# ZHSD-BOOT-STORAGE.net
KiCad netlist of a schematic drawn in Altium Designer
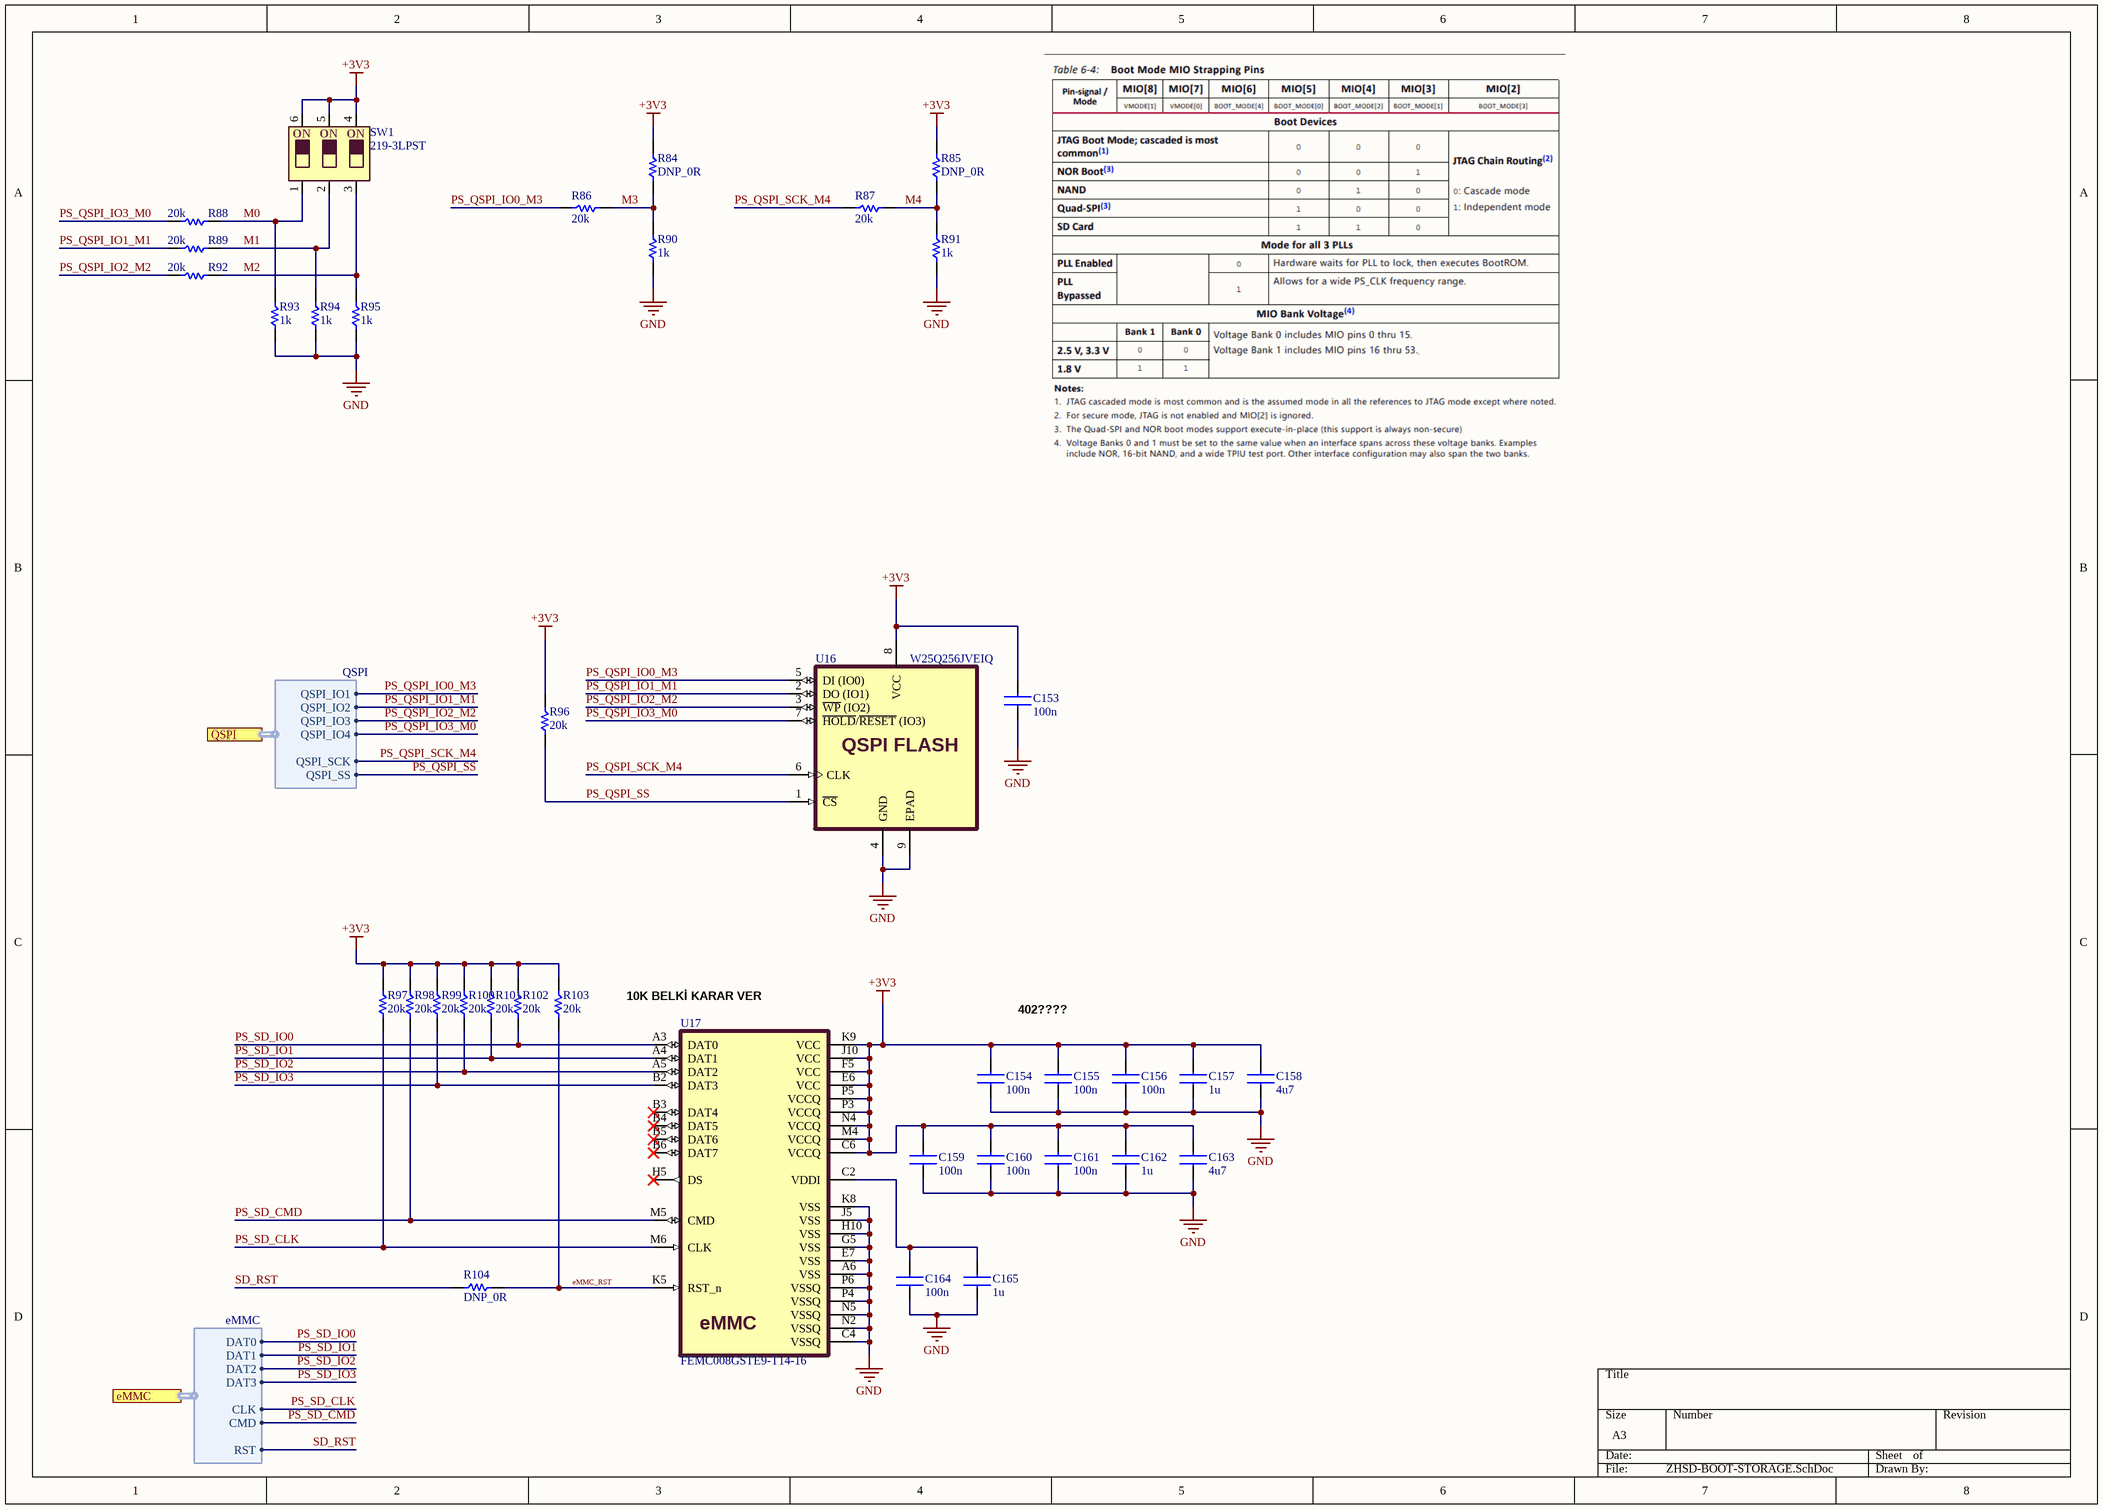
[diagram p0: ZHSD-BOOT-STORAGE.SchDoc]

(export (version "E")
  (design (tool "Eeschema 10.0.6"))
  (components
    (comp (ref "C153")
      (value "100n")
      (footprint "0603CAPC1608X09N")
      (description "CAP CER 0.1UF 16V X7R 0402 (1005) ±10%")
      (fields (field (name "MANUFACTURER") "Murata Electronics") (field (name "MPN") "GRM155R71C104KA88J"))
      (libsource (lib "UK_Library") (part "GRM155R71C104KA88J"))
    )
    (comp (ref "C154")
      (value "100n")
      (footprint "0603CAPC1608X09N")
      (description "CAP CER 0.1UF 16V X7R 0402 (1005) ±10%")
      (fields (field (name "MANUFACTURER") "Murata Electronics") (field (name "MPN") "GRM155R71C104KA88J"))
      (libsource (lib "UK_Library") (part "GRM155R71C104KA88J"))
    )
    (comp (ref "C155")
      (value "100n")
      (footprint "0603CAPC1608X09N")
      (description "CAP CER 0.1UF 16V X7R 0402 (1005) ±10%")
      (fields (field (name "MANUFACTURER") "Murata Electronics") (field (name "MPN") "GRM155R71C104KA88J"))
      (libsource (lib "UK_Library") (part "GRM155R71C104KA88J"))
    )
    (comp (ref "C156")
      (value "100n")
      (footprint "0603CAPC1608X09N")
      (description "CAP CER 0.1UF 16V X7R 0402 (1005) ±10%")
      (fields (field (name "MANUFACTURER") "Murata Electronics") (field (name "MPN") "GRM155R71C104KA88J"))
      (libsource (lib "UK_Library") (part "GRM155R71C104KA88J"))
    )
    (comp (ref "C157")
      (value "1u")
      (footprint "0603CAPC1608X09N")
      (description "CAP CER 1UF 25V X5R 0603 (1608) ±10%")
      (fields
        (field (name "MANUFACTURER") "Murata Power Solutions Inc.")
        (field (name "MPN") "GRM188R61E105KA12D")
      )
      (libsource (lib "UK_Library") (part "GRM188R61E105KA12D"))
    )
    (comp (ref "C158")
      (value "4u7")
      (footprint "0603CAPC1608X09N")
      (description "CAP CER 4.7UF 10V X5R 0603 (1608) ±10%")
      (fields
        (field (name "MANUFACTURER") "Samsung Electro-Mechanics")
        (field (name "MPN") "CL10A475KP8NNNC")
      )
      (libsource (lib "UK_Library") (part "CL10A475KP8NNNC"))
    )
    (comp (ref "C159")
      (value "100n")
      (footprint "0603CAPC1608X09N")
      (description "CAP CER 0.1UF 16V X7R 0402 (1005) ±10%")
      (fields (field (name "MANUFACTURER") "Murata Electronics") (field (name "MPN") "GRM155R71C104KA88J"))
      (libsource (lib "UK_Library") (part "GRM155R71C104KA88J"))
    )
    (comp (ref "C160")
      (value "100n")
      (footprint "0603CAPC1608X09N")
      (description "CAP CER 0.1UF 16V X7R 0402 (1005) ±10%")
      (fields (field (name "MANUFACTURER") "Murata Electronics") (field (name "MPN") "GRM155R71C104KA88J"))
      (libsource (lib "UK_Library") (part "GRM155R71C104KA88J"))
    )
    (comp (ref "C161")
      (value "100n")
      (footprint "0603CAPC1608X09N")
      (description "CAP CER 0.1UF 16V X7R 0402 (1005) ±10%")
      (fields (field (name "MANUFACTURER") "Murata Electronics") (field (name "MPN") "GRM155R71C104KA88J"))
      (libsource (lib "UK_Library") (part "GRM155R71C104KA88J"))
    )
    (comp (ref "C162")
      (value "1u")
      (footprint "0603CAPC1608X09N")
      (description "CAP CER 1UF 25V X5R 0603 (1608) ±10%")
      (fields
        (field (name "MANUFACTURER") "Murata Power Solutions Inc.")
        (field (name "MPN") "GRM188R61E105KA12D")
      )
      (libsource (lib "UK_Library") (part "GRM188R61E105KA12D"))
    )
    (comp (ref "C163")
      (value "4u7")
      (footprint "0603CAPC1608X09N")
      (description "CAP CER 4.7UF 10V X5R 0603 (1608) ±10%")
      (fields
        (field (name "MANUFACTURER") "Samsung Electro-Mechanics")
        (field (name "MPN") "CL10A475KP8NNNC")
      )
      (libsource (lib "UK_Library") (part "CL10A475KP8NNNC"))
    )
    (comp (ref "C164")
      (value "100n")
      (footprint "0603CAPC1608X09N")
      (description "CAP CER 0.1UF 16V X7R 0402 (1005) ±10%")
      (fields (field (name "MANUFACTURER") "Murata Electronics") (field (name "MPN") "GRM155R71C104KA88J"))
      (libsource (lib "UK_Library") (part "GRM155R71C104KA88J"))
    )
    (comp (ref "C165")
      (value "1u")
      (footprint "0603CAPC1608X09N")
      (description "CAP CER 1UF 25V X5R 0603 (1608) ±10%")
      (fields
        (field (name "MANUFACTURER") "Murata Power Solutions Inc.")
        (field (name "MPN") "GRM188R61E105KA12D")
      )
      (libsource (lib "UK_Library") (part "GRM188R61E105KA12D"))
    )
    (comp (ref "R84")
      (value "DNP_0R")
      (footprint "0402RESC1005X04N")
      (description "DO NOT POPULATE RESISTOR")
      (fields (field (name "MANUFACTURER") "***"))
      (libsource (lib "UK_Library") (part "DNP_RES"))
    )
    (comp (ref "R85")
      (value "DNP_0R")
      (footprint "0402RESC1005X04N")
      (description "DO NOT POPULATE RESISTOR")
      (fields (field (name "MANUFACTURER") "***"))
      (libsource (lib "UK_Library") (part "DNP_RES"))
    )
    (comp (ref "R86")
      (value "20k")
      (footprint "0402RESC1005X04N")
      (description "RES 20K OHM 1% 1/16W 0402 (1005)")
      (fields (field (name "MANUFACTURER") "YAGEO") (field (name "MPN") "RC0402FR-0720KL"))
      (libsource (lib "UK_Library") (part "RC0402FR-0720KL"))
    )
    (comp (ref "R87")
      (value "20k")
      (footprint "0402RESC1005X04N")
      (description "RES 20K OHM 1% 1/16W 0402 (1005)")
      (fields (field (name "MANUFACTURER") "YAGEO") (field (name "MPN") "RC0402FR-0720KL"))
      (libsource (lib "UK_Library") (part "RC0402FR-0720KL"))
    )
    (comp (ref "R88")
      (value "20k")
      (footprint "0402RESC1005X04N")
      (description "RES 20K OHM 1% 1/16W 0402 (1005)")
      (fields (field (name "MANUFACTURER") "YAGEO") (field (name "MPN") "RC0402FR-0720KL"))
      (libsource (lib "UK_Library") (part "RC0402FR-0720KL"))
    )
    (comp (ref "R89")
      (value "20k")
      (footprint "0402RESC1005X04N")
      (description "RES 20K OHM 1% 1/16W 0402 (1005)")
      (fields (field (name "MANUFACTURER") "YAGEO") (field (name "MPN") "RC0402FR-0720KL"))
      (libsource (lib "UK_Library") (part "RC0402FR-0720KL"))
    )
    (comp (ref "R90")
      (value "1k")
      (footprint "0402RESC1005X04N")
      (description "RES 1K OHM 5% 1/16W 0402 (1005)")
      (fields (field (name "MANUFACTURER") "YAGEO") (field (name "MPN") "RC0402JR-071KL"))
      (libsource (lib "UK_Library") (part "RC0402JR-071KL"))
    )
    (comp (ref "R91")
      (value "1k")
      (footprint "0402RESC1005X04N")
      (description "RES 1K OHM 5% 1/16W 0402 (1005)")
      (fields (field (name "MANUFACTURER") "YAGEO") (field (name "MPN") "RC0402JR-071KL"))
      (libsource (lib "UK_Library") (part "RC0402JR-071KL"))
    )
    (comp (ref "R92")
      (value "20k")
      (footprint "0402RESC1005X04N")
      (description "RES 20K OHM 1% 1/16W 0402 (1005)")
      (fields (field (name "MANUFACTURER") "YAGEO") (field (name "MPN") "RC0402FR-0720KL"))
      (libsource (lib "UK_Library") (part "RC0402FR-0720KL"))
    )
    (comp (ref "R93")
      (value "1k")
      (footprint "0402RESC1005X04N")
      (description "RES 1K OHM 5% 1/16W 0402 (1005)")
      (fields (field (name "MANUFACTURER") "YAGEO") (field (name "MPN") "RC0402JR-071KL"))
      (libsource (lib "UK_Library") (part "RC0402JR-071KL"))
    )
    (comp (ref "R94")
      (value "1k")
      (footprint "0402RESC1005X04N")
      (description "RES 1K OHM 5% 1/16W 0402 (1005)")
      (fields (field (name "MANUFACTURER") "YAGEO") (field (name "MPN") "RC0402JR-071KL"))
      (libsource (lib "UK_Library") (part "RC0402JR-071KL"))
    )
    (comp (ref "R95")
      (value "1k")
      (footprint "0402RESC1005X04N")
      (description "RES 1K OHM 5% 1/16W 0402 (1005)")
      (fields (field (name "MANUFACTURER") "YAGEO") (field (name "MPN") "RC0402JR-071KL"))
      (libsource (lib "UK_Library") (part "RC0402JR-071KL"))
    )
    (comp (ref "R96")
      (value "20k")
      (footprint "0402RESC1005X04N")
      (description "RES 20K OHM 1% 1/16W 0402 (1005)")
      (fields (field (name "MANUFACTURER") "YAGEO") (field (name "MPN") "RC0402FR-0720KL"))
      (libsource (lib "UK_Library") (part "RC0402FR-0720KL"))
    )
    (comp (ref "R97")
      (value "20k")
      (footprint "0402RESC1005X04N")
      (description "RES 20K OHM 1% 1/16W 0402 (1005)")
      (fields (field (name "MANUFACTURER") "YAGEO") (field (name "MPN") "RC0402FR-0720KL"))
      (libsource (lib "UK_Library") (part "RC0402FR-0720KL"))
    )
    (comp (ref "R98")
      (value "20k")
      (footprint "0402RESC1005X04N")
      (description "RES 20K OHM 1% 1/16W 0402 (1005)")
      (fields (field (name "MANUFACTURER") "YAGEO") (field (name "MPN") "RC0402FR-0720KL"))
      (libsource (lib "UK_Library") (part "RC0402FR-0720KL"))
    )
    (comp (ref "R99")
      (value "20k")
      (footprint "0402RESC1005X04N")
      (description "RES 20K OHM 1% 1/16W 0402 (1005)")
      (fields (field (name "MANUFACTURER") "YAGEO") (field (name "MPN") "RC0402FR-0720KL"))
      (libsource (lib "UK_Library") (part "RC0402FR-0720KL"))
    )
    (comp (ref "R100")
      (value "20k")
      (footprint "0402RESC1005X04N")
      (description "RES 20K OHM 1% 1/16W 0402 (1005)")
      (fields (field (name "MANUFACTURER") "YAGEO") (field (name "MPN") "RC0402FR-0720KL"))
      (libsource (lib "UK_Library") (part "RC0402FR-0720KL"))
    )
    (comp (ref "R101")
      (value "20k")
      (footprint "0402RESC1005X04N")
      (description "RES 20K OHM 1% 1/16W 0402 (1005)")
      (fields (field (name "MANUFACTURER") "YAGEO") (field (name "MPN") "RC0402FR-0720KL"))
      (libsource (lib "UK_Library") (part "RC0402FR-0720KL"))
    )
    (comp (ref "R102")
      (value "20k")
      (footprint "0402RESC1005X04N")
      (description "RES 20K OHM 1% 1/16W 0402 (1005)")
      (fields (field (name "MANUFACTURER") "YAGEO") (field (name "MPN") "RC0402FR-0720KL"))
      (libsource (lib "UK_Library") (part "RC0402FR-0720KL"))
    )
    (comp (ref "R103")
      (value "20k")
      (footprint "0402RESC1005X04N")
      (description "RES 20K OHM 1% 1/16W 0402 (1005)")
      (fields (field (name "MANUFACTURER") "YAGEO") (field (name "MPN") "RC0402FR-0720KL"))
      (libsource (lib "UK_Library") (part "RC0402FR-0720KL"))
    )
    (comp (ref "R104")
      (value "DNP_0R")
      (footprint "0402RESC1005X04N")
      (description "DO NOT POPULATE RESISTOR")
      (fields (field (name "MANUFACTURER") "***"))
      (libsource (lib "UK_Library") (part "DNP_RES"))
    )
    (comp (ref "SW1")
      (value "219-3LPST")
      (footprint "219-3LPST")
      (description "Dip Switch SPST 3 Position Surface Mount Slide (Standard) Actuator 100mA 20VDC")
      (fields (field (name "MANUFACTURER") "CTS Electrocomponents"))
      (libsource (lib "UK_Library_SCH") (part "219-3LPST"))
    )
    (comp (ref "U16")
      (value "W25Q256JVEIQ")
      (footprint "WSON8X6-SON127P800X80_HS-9N")
      (description "FLASH - NOR Memory IC 256Mbit SPI - Quad I/O 133 MHz 8-WSON (8x6)")
      (fields (field (name "MANUFACTURER") "Winbond Electronics"))
      (libsource (lib "UK_Library") (part "W25Q256JVEIQ"))
    )
    (comp (ref "U17")
      (value "FEMC008GSTE9-T14-16")
      (footprint "BGA153C50P14X14_1150X1300X100")
      (description "FLASH - NAND (MLC) Memory IC 64Gbit eMMC_5.1 200 MHz 153-FBGA (11.5x13)")
      (fields (field (name "MANUFACTURER") "Flexxon Pte Ltd"))
      (libsource (lib "UK_Library") (part "FEMC008GSTE9-T14-16"))
    )
  )
  (nets
    (net (code "3") (name "+3V3") (class "Default")
      (node (ref "C153") (pin "2") (pinfunction "2_2") (pintype "passive"))
      (node (ref "C154") (pin "2") (pinfunction "2_2") (pintype "passive"))
      (node (ref "C155") (pin "2") (pinfunction "2_2") (pintype "passive"))
      (node (ref "C156") (pin "2") (pinfunction "2_2") (pintype "passive"))
      (node (ref "C157") (pin "2") (pinfunction "2_2") (pintype "passive"))
      (node (ref "C158") (pin "2") (pinfunction "2_2") (pintype "passive"))
      (node (ref "C159") (pin "2") (pinfunction "2_2") (pintype "passive"))
      (node (ref "C160") (pin "2") (pinfunction "2_2") (pintype "passive"))
      (node (ref "C161") (pin "2") (pinfunction "2_2") (pintype "passive"))
      (node (ref "C162") (pin "2") (pinfunction "2_2") (pintype "passive"))
      (node (ref "C163") (pin "2") (pinfunction "2_2") (pintype "passive"))
      (node (ref "R100") (pin "2") (pinfunction "2_2") (pintype "passive"))
      (node (ref "R101") (pin "2") (pinfunction "2_2") (pintype "passive"))
      (node (ref "R102") (pin "2") (pinfunction "2_2") (pintype "passive"))
      (node (ref "R103") (pin "2") (pinfunction "2_2") (pintype "passive"))
      (node (ref "R84") (pin "2") (pinfunction "2_2") (pintype "passive"))
      (node (ref "R85") (pin "2") (pinfunction "2_2") (pintype "passive"))
      (node (ref "R96") (pin "2") (pinfunction "2_2") (pintype "passive"))
      (node (ref "R97") (pin "2") (pinfunction "2_2") (pintype "passive"))
      (node (ref "R98") (pin "2") (pinfunction "2_2") (pintype "passive"))
      (node (ref "R99") (pin "2") (pinfunction "2_2") (pintype "passive"))
      (node (ref "SW1") (pin "4") (pinfunction "4_4") (pintype "passive"))
      (node (ref "SW1") (pin "5") (pinfunction "5_5") (pintype "passive"))
      (node (ref "SW1") (pin "6") (pinfunction "6_6") (pintype "passive"))
      (node (ref "U16") (pin "8") (pinfunction "VCC_8") (pintype "power_in"))
      (node (ref "U17") (pin "C6") (pinfunction "VCCQ_C6") (pintype "power_in"))
      (node (ref "U17") (pin "E6") (pinfunction "VCC_E6") (pintype "power_in"))
      (node (ref "U17") (pin "F5") (pinfunction "VCC_F5") (pintype "power_in"))
      (node (ref "U17") (pin "J10") (pinfunction "VCC_J10") (pintype "power_in"))
      (node (ref "U17") (pin "K9") (pinfunction "VCC_K9") (pintype "power_in"))
      (node (ref "U17") (pin "M4") (pinfunction "VCCQ_M4") (pintype "power_in"))
      (node (ref "U17") (pin "N4") (pinfunction "VCCQ_N4") (pintype "power_in"))
      (node (ref "U17") (pin "P3") (pinfunction "VCCQ_P3") (pintype "power_in"))
      (node (ref "U17") (pin "P5") (pinfunction "VCCQ_P5") (pintype "power_in"))
    )
    (net (code "4") (name "/M0") (class "Default")
      (node (ref "R88") (pin "1") (pinfunction "1_1") (pintype "passive"))
      (node (ref "R93") (pin "2") (pinfunction "2_2") (pintype "passive"))
      (node (ref "SW1") (pin "1") (pinfunction "1_1") (pintype "passive"))
    )
    (net (code "5") (name "/M1") (class "Default")
      (node (ref "R89") (pin "1") (pinfunction "1_1") (pintype "passive"))
      (node (ref "R94") (pin "2") (pinfunction "2_2") (pintype "passive"))
      (node (ref "SW1") (pin "2") (pinfunction "2_2") (pintype "passive"))
    )
    (net (code "6") (name "/M2") (class "Default")
      (node (ref "R92") (pin "1") (pinfunction "1_1") (pintype "passive"))
      (node (ref "R95") (pin "2") (pinfunction "2_2") (pintype "passive"))
      (node (ref "SW1") (pin "3") (pinfunction "3_3") (pintype "passive"))
    )
    (net (code "7") (name "/M3") (class "Default")
      (node (ref "R84") (pin "1") (pinfunction "1_1") (pintype "passive"))
      (node (ref "R86") (pin "1") (pinfunction "1_1") (pintype "passive"))
      (node (ref "R90") (pin "2") (pinfunction "2_2") (pintype "passive"))
    )
    (net (code "8") (name "/M4") (class "Default")
      (node (ref "R85") (pin "1") (pinfunction "1_1") (pintype "passive"))
      (node (ref "R87") (pin "1") (pinfunction "1_1") (pintype "passive"))
      (node (ref "R91") (pin "2") (pinfunction "2_2") (pintype "passive"))
    )
    (net (code "9") (name "/PS_QSPI_IO0_M3") (class "Default")
      (node (ref "R86") (pin "2") (pinfunction "2_2") (pintype "passive"))
      (node (ref "U16") (pin "5") (pinfunction "DI_(IO0)_5") (pintype "bidirectional"))
    )
    (net (code "10") (name "/PS_QSPI_IO1_M1") (class "Default")
      (node (ref "R89") (pin "2") (pinfunction "2_2") (pintype "passive"))
      (node (ref "U16") (pin "2") (pinfunction "DO_(IO1)_2") (pintype "bidirectional"))
    )
    (net (code "11") (name "/PS_QSPI_IO2_M2") (class "Default")
      (node (ref "R92") (pin "2") (pinfunction "2_2") (pintype "passive"))
      (node (ref "U16") (pin "3") (pinfunction "~{WP}_(IO2)_3") (pintype "bidirectional"))
    )
    (net (code "12") (name "/PS_QSPI_IO3_M0") (class "Default")
      (node (ref "R88") (pin "2") (pinfunction "2_2") (pintype "passive"))
      (node (ref "U16") (pin "7") (pinfunction "~{HOLD}/~{RESET}_(IO3)_7") (pintype "bidirectional"))
    )
    (net (code "13") (name "/PS_QSPI_SCK_M4") (class "Default")
      (node (ref "R87") (pin "2") (pinfunction "2_2") (pintype "passive"))
      (node (ref "U16") (pin "6") (pinfunction "CLK_6") (pintype "input"))
    )
    (net (code "14") (name "/PS_QSPI_SS") (class "Default")
      (node (ref "R96") (pin "1") (pinfunction "1_1") (pintype "passive"))
      (node (ref "U16") (pin "1") (pinfunction "~{CS}_1") (pintype "input"))
    )
    (net (code "15") (name "/PS_SD_CLK") (class "Default")
      (node (ref "R97") (pin "1") (pinfunction "1_1") (pintype "passive"))
      (node (ref "U17") (pin "M6") (pinfunction "CLK_M6") (pintype "input"))
    )
    (net (code "16") (name "/PS_SD_CMD") (class "Default")
      (node (ref "R98") (pin "1") (pinfunction "1_1") (pintype "passive"))
      (node (ref "U17") (pin "M5") (pinfunction "CMD_M5") (pintype "bidirectional"))
    )
    (net (code "17") (name "/PS_SD_IO0") (class "Default")
      (node (ref "R102") (pin "1") (pinfunction "1_1") (pintype "passive"))
      (node (ref "U17") (pin "A3") (pinfunction "DAT0_A3") (pintype "bidirectional"))
    )
    (net (code "18") (name "/PS_SD_IO1") (class "Default")
      (node (ref "R101") (pin "1") (pinfunction "1_1") (pintype "passive"))
      (node (ref "U17") (pin "A4") (pinfunction "DAT1_A4") (pintype "bidirectional"))
    )
    (net (code "19") (name "/PS_SD_IO2") (class "Default")
      (node (ref "R100") (pin "1") (pinfunction "1_1") (pintype "passive"))
      (node (ref "U17") (pin "A5") (pinfunction "DAT2_A5") (pintype "bidirectional"))
    )
    (net (code "20") (name "/PS_SD_IO3") (class "Default")
      (node (ref "R99") (pin "1") (pinfunction "1_1") (pintype "passive"))
      (node (ref "U17") (pin "B2") (pinfunction "DAT3_B2") (pintype "bidirectional"))
    )
    (net (code "21") (name "/SD_RST") (class "Default")
      (node (ref "R104") (pin "1") (pinfunction "1_1") (pintype "passive"))
    )
    (net (code "22") (name "/eMMC_RST") (class "Default")
      (node (ref "R103") (pin "1") (pinfunction "1_1") (pintype "passive"))
      (node (ref "R104") (pin "2") (pinfunction "2_2") (pintype "passive"))
      (node (ref "U17") (pin "K5") (pinfunction "RST_n_K5") (pintype "input"))
    )
    (net (code "25") (name "GND") (class "Default")
      (node (ref "C153") (pin "1") (pinfunction "1_1") (pintype "passive"))
      (node (ref "C154") (pin "1") (pinfunction "1_1") (pintype "passive"))
      (node (ref "C155") (pin "1") (pinfunction "1_1") (pintype "passive"))
      (node (ref "C156") (pin "1") (pinfunction "1_1") (pintype "passive"))
      (node (ref "C157") (pin "1") (pinfunction "1_1") (pintype "passive"))
      (node (ref "C158") (pin "1") (pinfunction "1_1") (pintype "passive"))
      (node (ref "C159") (pin "1") (pinfunction "1_1") (pintype "passive"))
      (node (ref "C160") (pin "1") (pinfunction "1_1") (pintype "passive"))
      (node (ref "C161") (pin "1") (pinfunction "1_1") (pintype "passive"))
      (node (ref "C162") (pin "1") (pinfunction "1_1") (pintype "passive"))
      (node (ref "C163") (pin "1") (pinfunction "1_1") (pintype "passive"))
      (node (ref "C164") (pin "1") (pinfunction "1_1") (pintype "passive"))
      (node (ref "C165") (pin "1") (pinfunction "1_1") (pintype "passive"))
      (node (ref "R90") (pin "1") (pinfunction "1_1") (pintype "passive"))
      (node (ref "R91") (pin "1") (pinfunction "1_1") (pintype "passive"))
      (node (ref "R93") (pin "1") (pinfunction "1_1") (pintype "passive"))
      (node (ref "R94") (pin "1") (pinfunction "1_1") (pintype "passive"))
      (node (ref "R95") (pin "1") (pinfunction "1_1") (pintype "passive"))
      (node (ref "U16") (pin "4") (pinfunction "GND_4") (pintype "power_in"))
      (node (ref "U16") (pin "9") (pinfunction "EPAD_9") (pintype "power_in"))
      (node (ref "U17") (pin "A6") (pinfunction "VSS_A6") (pintype "power_in"))
      (node (ref "U17") (pin "C4") (pinfunction "VSSQ_C4") (pintype "power_in"))
      (node (ref "U17") (pin "E7") (pinfunction "VSS_E7") (pintype "power_in"))
      (node (ref "U17") (pin "G5") (pinfunction "VSS_G5") (pintype "power_in"))
      (node (ref "U17") (pin "H10") (pinfunction "VSS_H10") (pintype "power_in"))
      (node (ref "U17") (pin "J5") (pinfunction "VSS_J5") (pintype "power_in"))
      (node (ref "U17") (pin "K8") (pinfunction "VSS_K8") (pintype "power_in"))
      (node (ref "U17") (pin "N2") (pinfunction "VSSQ_N2") (pintype "power_in"))
      (node (ref "U17") (pin "N5") (pinfunction "VSSQ_N5") (pintype "power_in"))
      (node (ref "U17") (pin "P4") (pinfunction "VSSQ_P4") (pintype "power_in"))
      (node (ref "U17") (pin "P6") (pinfunction "VSSQ_P6") (pintype "power_in"))
    )
    (net (code "26") (name "Net-(U17-VDDI)") (class "Default")
      (node (ref "C164") (pin "2") (pinfunction "2_2") (pintype "passive"))
      (node (ref "C165") (pin "2") (pinfunction "2_2") (pintype "passive"))
      (node (ref "U17") (pin "C2") (pinfunction "VDDI_C2") (pintype "power_in"))
    )
    (net (code "27") (name "unconnected-(U17-DAT4-PadB3)") (class "Default")
      (node (ref "U17") (pin "B3") (pinfunction "DAT4_B3") (pintype "bidirectional+no_connect"))
    )
    (net (code "28") (name "unconnected-(U17-DAT5-PadB4)") (class "Default")
      (node (ref "U17") (pin "B4") (pinfunction "DAT5_B4") (pintype "bidirectional+no_connect"))
    )
    (net (code "29") (name "unconnected-(U17-DAT6-PadB5)") (class "Default")
      (node (ref "U17") (pin "B5") (pinfunction "DAT6_B5") (pintype "bidirectional+no_connect"))
    )
    (net (code "30") (name "unconnected-(U17-DAT7-PadB6)") (class "Default")
      (node (ref "U17") (pin "B6") (pinfunction "DAT7_B6") (pintype "bidirectional+no_connect"))
    )
    (net (code "31") (name "unconnected-(U17-DS-PadH5)") (class "Default")
      (node (ref "U17") (pin "H5") (pinfunction "DS_H5") (pintype "output+no_connect"))
    )
  )
)
